# Joystick_Module_A.net
KiCad netlist of a schematic drawn in EAGLE
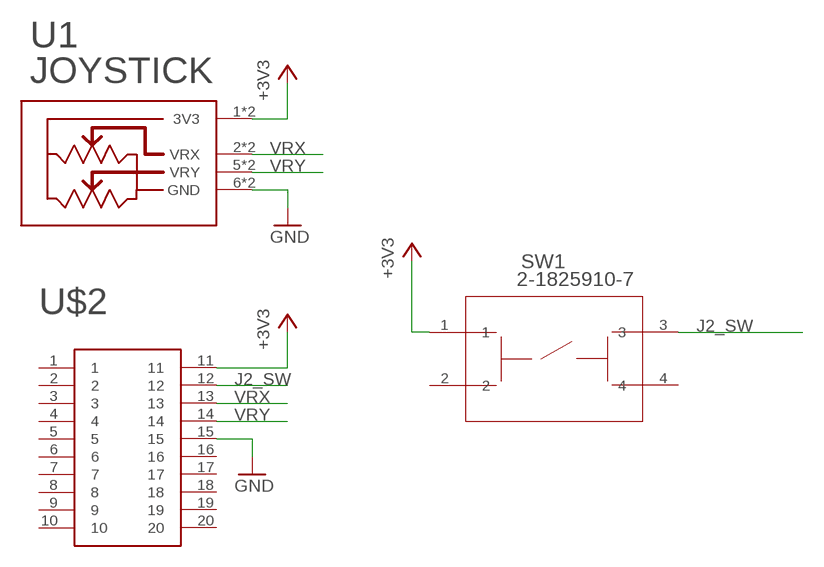
[diagram p0: schematic, sheet 1]

(export (version "E")
  (design (tool "Eeschema 10.0.6"))
  (components
    (comp (ref "SW1")
      (value "2-1825910-7")
      (footprint "eagle-import:SW4_1825910-G")
      (fields (field (name "MANUFACTURER_PART_NUMBER") "218259107"))
      (libsource (lib "eagle-import") (part "2-1825910-7"))
    )
    (comp (ref "U$2")
      (value "EDGE_CONNECTOR_20POS_CONTACTS")
      (footprint "eagle-import:EDGE_CONNECTOR_20POS_CONTACTS")
      (libsource (lib "eagle-import") (part "EDGE_CONNECTOR_20POS_CONTACTS"))
    )
    (comp (ref "U1")
      (value "27800-JOYSTICK")
      (footprint "eagle-import:27800-JOYSTICK")
      (libsource (lib "eagle-import") (part "27800-JOYSTICK"))
    )
  )
  (nets
    (net (code "1") (name "+3V3") (class "Default")
      (node (ref "SW1") (pin "1") (pinfunction "1_1") (pintype "passive"))
      (node (ref "U$2") (pin "11") (pinfunction "11_11") (pintype "bidirectional"))
      (node (ref "U1") (pin "1") (pinfunction "3V3_1") (pintype "power_in"))
      (node (ref "U1") (pin "3") (pinfunction "3V3_3") (pintype "power_in"))
    )
    (net (code "2") (name "/J2_SW") (class "Default")
      (node (ref "SW1") (pin "3") (pinfunction "3_3") (pintype "passive"))
      (node (ref "U$2") (pin "12") (pinfunction "12_12") (pintype "bidirectional"))
    )
    (net (code "3") (name "/VRX") (class "Default")
      (node (ref "U$2") (pin "13") (pinfunction "13_13") (pintype "bidirectional"))
      (node (ref "U1") (pin "2") (pinfunction "VRX_2") (pintype "bidirectional"))
      (node (ref "U1") (pin "4") (pinfunction "VRX_4") (pintype "bidirectional"))
    )
    (net (code "4") (name "/VRY") (class "Default")
      (node (ref "U$2") (pin "14") (pinfunction "14_14") (pintype "bidirectional"))
      (node (ref "U1") (pin "5") (pinfunction "VRY_5") (pintype "bidirectional"))
      (node (ref "U1") (pin "7") (pinfunction "VRY_7") (pintype "bidirectional"))
    )
    (net (code "5") (name "GND") (class "Default")
      (node (ref "U$2") (pin "15") (pinfunction "15_15") (pintype "bidirectional"))
      (node (ref "U1") (pin "6") (pinfunction "GND_6") (pintype "power_in"))
      (node (ref "U1") (pin "8") (pinfunction "GND_8") (pintype "power_in"))
    )
    (net (code "6") (name "unconnected-(SW1-Pad2)") (class "Default")
      (node (ref "SW1") (pin "2") (pinfunction "2_2") (pintype "passive"))
    )
    (net (code "7") (name "unconnected-(SW1-Pad4)") (class "Default")
      (node (ref "SW1") (pin "4") (pinfunction "4_4") (pintype "passive"))
    )
    (net (code "8") (name "unconnected-(U$2-Pad1)") (class "Default")
      (node (ref "U$2") (pin "1") (pinfunction "1_1") (pintype "bidirectional"))
    )
    (net (code "9") (name "unconnected-(U$2-Pad2)") (class "Default")
      (node (ref "U$2") (pin "2") (pinfunction "2_2") (pintype "bidirectional"))
    )
    (net (code "10") (name "unconnected-(U$2-Pad3)") (class "Default")
      (node (ref "U$2") (pin "3") (pinfunction "3_3") (pintype "bidirectional"))
    )
    (net (code "11") (name "unconnected-(U$2-Pad4)") (class "Default")
      (node (ref "U$2") (pin "4") (pinfunction "4_4") (pintype "bidirectional"))
    )
    (net (code "12") (name "unconnected-(U$2-Pad5)") (class "Default")
      (node (ref "U$2") (pin "5") (pinfunction "5_5") (pintype "bidirectional"))
    )
    (net (code "13") (name "unconnected-(U$2-Pad6)") (class "Default")
      (node (ref "U$2") (pin "6") (pinfunction "6_6") (pintype "bidirectional"))
    )
    (net (code "14") (name "unconnected-(U$2-Pad7)") (class "Default")
      (node (ref "U$2") (pin "7") (pinfunction "7_7") (pintype "bidirectional"))
    )
    (net (code "15") (name "unconnected-(U$2-Pad8)") (class "Default")
      (node (ref "U$2") (pin "8") (pinfunction "8_8") (pintype "bidirectional"))
    )
    (net (code "16") (name "unconnected-(U$2-Pad9)") (class "Default")
      (node (ref "U$2") (pin "9") (pinfunction "9_9") (pintype "bidirectional"))
    )
    (net (code "17") (name "unconnected-(U$2-Pad10)") (class "Default")
      (node (ref "U$2") (pin "10") (pinfunction "10_10") (pintype "bidirectional"))
    )
    (net (code "18") (name "unconnected-(U$2-Pad16)") (class "Default")
      (node (ref "U$2") (pin "16") (pinfunction "16_16") (pintype "bidirectional"))
    )
    (net (code "19") (name "unconnected-(U$2-Pad17)") (class "Default")
      (node (ref "U$2") (pin "17") (pinfunction "17_17") (pintype "bidirectional"))
    )
    (net (code "20") (name "unconnected-(U$2-Pad18)") (class "Default")
      (node (ref "U$2") (pin "18") (pinfunction "18_18") (pintype "bidirectional"))
    )
    (net (code "21") (name "unconnected-(U$2-Pad19)") (class "Default")
      (node (ref "U$2") (pin "19") (pinfunction "19_19") (pintype "bidirectional"))
    )
    (net (code "22") (name "unconnected-(U$2-Pad20)") (class "Default")
      (node (ref "U$2") (pin "20") (pinfunction "20_20") (pintype "bidirectional"))
    )
  )
)
